# 01_Power.net
KiCad netlist of a schematic drawn in Altium Designer
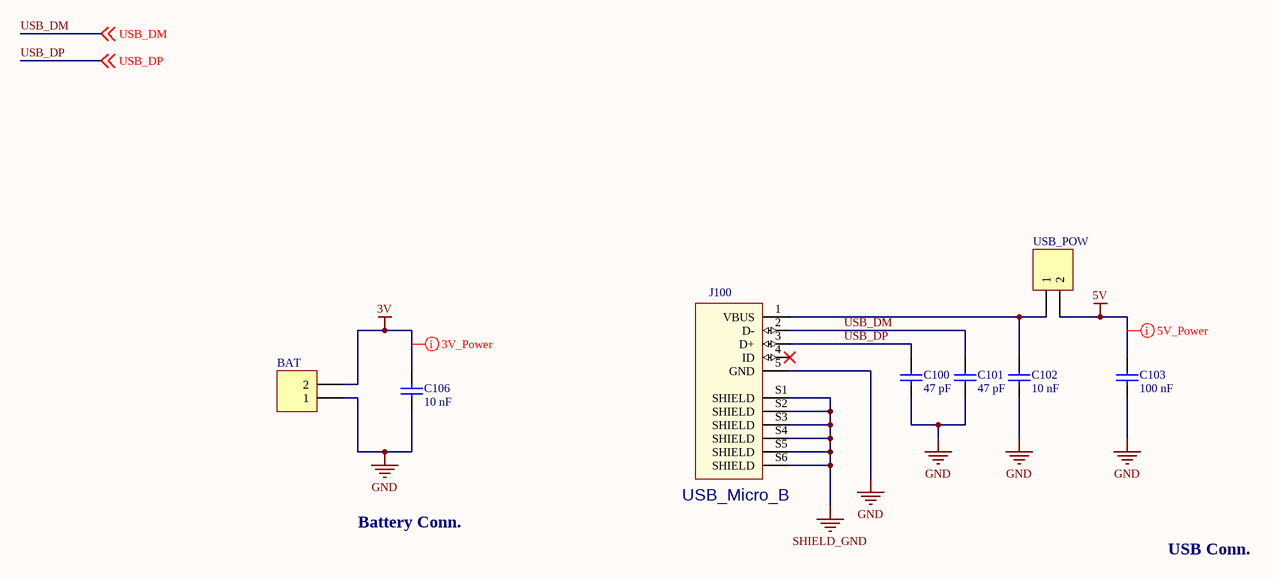
[diagram p0: 01_Power.SchDoc]

(export (version "E")
  (design (tool "Eeschema 10.0.6"))
  (components
    (comp (ref "BAT")
      (value "~")
      (footprint "HDR1X2")
      (description "Header, 2-Pin")
      (fields (field (name "PUBLISHER") "Altium Limited"))
      (libsource (lib "Miscellaneous Connectors") (part "Header 2"))
    )
    (comp (ref "C100")
      (value "47 pF")
      (footprint "C0805")
      (description "CAP CER 47PF 1KV C0G/NP0 0805")
      (fields
        (field (name "MANUFACTURER") "KEMET")
        (field (name "MANUFACTURER PART NUMBER") "C0805C470JDGACTU")
      )
      (libsource (lib "temperature_logger_lib") (part "Cap-47pF"))
    )
    (comp (ref "C101")
      (value "47 pF")
      (footprint "C0805")
      (description "CAP CER 47PF 1KV C0G/NP0 0805")
      (fields
        (field (name "MANUFACTURER") "KEMET")
        (field (name "MANUFACTURER PART NUMBER") "C0805C470JDGACTU")
      )
      (libsource (lib "temperature_logger_lib") (part "Cap-47pF"))
    )
    (comp (ref "C102")
      (value "10 nF")
      (footprint "C0805")
      (description "CAP CER 10000PF 10V X7R 0805")
      (fields
        (field (name "MANUFACTURER") "Wurth Electronics Inc.")
        (field (name "MANUFACTURER PART NUMBER") "885012207011")
      )
      (libsource (lib "temperature_logger_lib") (part "Cap-10nF"))
    )
    (comp (ref "C103")
      (value "100 nF")
      (footprint "C0805")
      (description "CAP CER 0.1UF 50V X7R 0805")
      (fields
        (field (name "MANUFACTURER") "KEMET")
        (field (name "MANUFACTURER PART NUMBER") "C0805X104K5RACTU")
      )
      (libsource (lib "temperature_logger_lib") (part "Cap-100nF"))
    )
    (comp (ref "C106")
      (value "10 nF")
      (footprint "C0805")
      (description "CAP CER 10000PF 10V X7R 0805")
      (fields
        (field (name "MANUFACTURER") "Wurth Electronics Inc.")
        (field (name "MANUFACTURER PART NUMBER") "885012207011")
      )
      (libsource (lib "temperature_logger_lib") (part "Cap-10nF"))
    )
    (comp (ref "J100")
      (value "USB_Micro_B")
      (footprint "MicroUSB")
      (description "USB - micro B USB 2.0 Receptacle Connector 5 Position Surface Mount, Right Angle; Through Hole")
      (fields
        (field (name "MANUFACTURER PART NUMBER") "2040002-1")
        (field (name "MANUFACTURER") "TE Connectivity")
      )
      (libsource (lib "temperature_logger_lib") (part "USB_Micro_B"))
    )
    (comp (ref "USB_POW")
      (value "~")
      (footprint "HDR1X2")
      (description "Header, 2-Pin")
      (fields (field (name "PUBLISHER") "Altium Limited"))
      (libsource (lib "") (part "Header 2_1"))
    )
  )
  (nets
    (net (code "1") (name "3V") (class "Default")
      (node (ref "BAT") (pin "2") (pinfunction "2_2") (pintype "passive"))
      (node (ref "C106") (pin "2") (pinfunction "2_2") (pintype "passive"))
    )
    (net (code "2") (name "5V") (class "Default")
      (node (ref "C103") (pin "2") (pinfunction "2_2") (pintype "passive"))
      (node (ref "USB_POW") (pin "2") (pinfunction "2_2") (pintype "passive"))
    )
    (net (code "3") (name "GND") (class "Default")
      (node (ref "BAT") (pin "1") (pinfunction "1_1") (pintype "passive"))
      (node (ref "C100") (pin "1") (pinfunction "1_1") (pintype "passive"))
      (node (ref "C101") (pin "1") (pinfunction "1_1") (pintype "passive"))
      (node (ref "C102") (pin "1") (pinfunction "1_1") (pintype "passive"))
      (node (ref "C103") (pin "1") (pinfunction "1_1") (pintype "passive"))
      (node (ref "C106") (pin "1") (pinfunction "1_1") (pintype "passive"))
      (node (ref "J100") (pin "5") (pinfunction "GND_5") (pintype "power_in"))
    )
    (net (code "4") (name "Net-(J100-VBUS)") (class "Default")
      (node (ref "C102") (pin "2") (pinfunction "2_2") (pintype "passive"))
      (node (ref "J100") (pin "1") (pinfunction "VBUS_1") (pintype "power_in"))
      (node (ref "USB_POW") (pin "1") (pinfunction "1_1") (pintype "passive"))
    )
    (net (code "5") (name "SHIELD_GND") (class "Default")
      (node (ref "J100") (pin "S1") (pinfunction "SHIELD_S1") (pintype "power_in"))
      (node (ref "J100") (pin "S2") (pinfunction "SHIELD_S2") (pintype "power_in"))
      (node (ref "J100") (pin "S3") (pinfunction "SHIELD_S3") (pintype "power_in"))
      (node (ref "J100") (pin "S4") (pinfunction "SHIELD_S4") (pintype "power_in"))
      (node (ref "J100") (pin "S5") (pinfunction "SHIELD_S5") (pintype "power_in"))
      (node (ref "J100") (pin "S6") (pinfunction "SHIELD_S6") (pintype "power_in"))
    )
    (net (code "6") (name "USB_DM") (class "Default")
      (node (ref "C101") (pin "2") (pinfunction "2_2") (pintype "passive"))
      (node (ref "J100") (pin "2") (pinfunction "D-_2") (pintype "bidirectional"))
    )
    (net (code "7") (name "USB_DP") (class "Default")
      (node (ref "C100") (pin "2") (pinfunction "2_2") (pintype "passive"))
      (node (ref "J100") (pin "3") (pinfunction "D+_3") (pintype "bidirectional"))
    )
    (net (code "8") (name "unconnected-(J100-ID-Pad4)") (class "Default")
      (node (ref "J100") (pin "4") (pinfunction "ID_4") (pintype "bidirectional+no_connect"))
    )
  )
)
